# Sheet1.net
KiCad netlist of a schematic drawn in Altium Designer
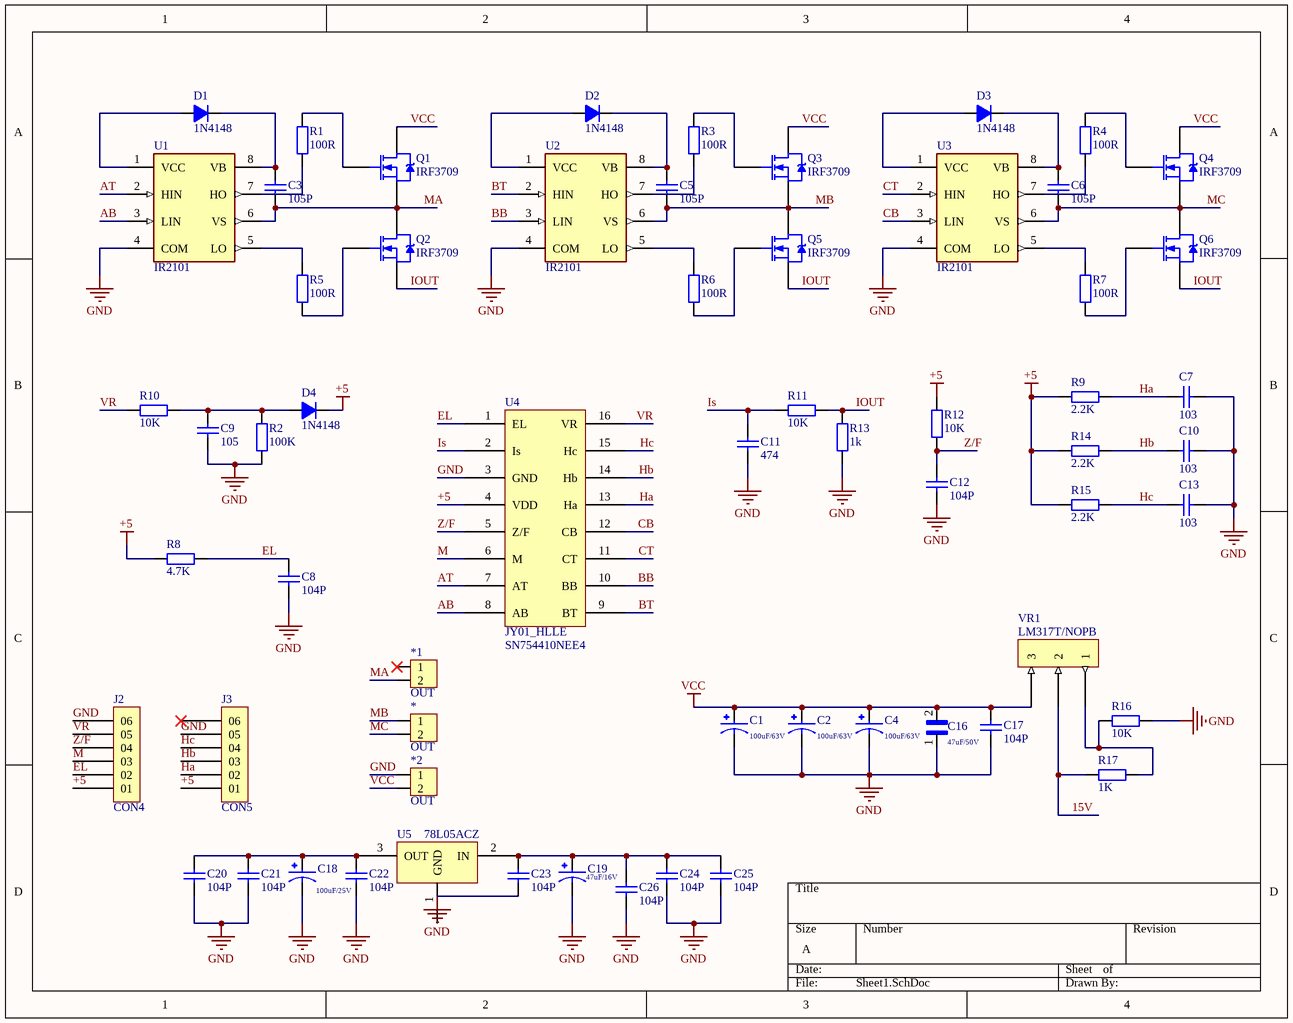
[diagram p0: Sheet1.SchDoc]

(export (version "E")
  (design (tool "Eeschema 10.0.6"))
  (components
    (comp (ref "*")
      (value "OUT")
      (footprint "VH3.96M-2 CONG")
      (libsource (lib "Altium_Duc Le_Lib(1)") (part "Header 2P VH3.96 Duc Cong"))
    )
    (comp (ref "*1")
      (value "OUT")
      (footprint "VH3.96M-2 CONG")
      (libsource (lib "Altium_Duc Le_Lib(1)") (part "Header 2P VH3.96 Duc Cong"))
    )
    (comp (ref "*2")
      (value "OUT")
      (footprint "VH3.96M-2 CONG")
      (libsource (lib "Altium_Duc Le_Lib(1)") (part "Header 2P VH3.96 Duc Cong"))
    )
    (comp (ref "C1")
      (value "100uF/63V")
      (footprint "CAP_EEVTG1J101Q")
      (description "100ÂµF 63V Aluminum Electrolytic Capacitors Radial, Can - SMD 260mOhm @ 100kHz 2000 Hrs @ 125Â°C")
      (fields (field (name "MP") "EEVTG1J101Q") (field (name "MF") "Panasonic"))
      (libsource (lib "100uF63VAEC") (part "EEVTG1J101Q"))
    )
    (comp (ref "C2")
      (value "100uF/63V")
      (footprint "CAP_EEVTG1J101Q")
      (description "100ÂµF 63V Aluminum Electrolytic Capacitors Radial, Can - SMD 260mOhm @ 100kHz 2000 Hrs @ 125Â°C")
      (fields (field (name "MP") "EEVTG1J101Q") (field (name "MF") "Panasonic"))
      (libsource (lib "100uF63VAEC") (part "EEVTG1J101Q"))
    )
    (comp (ref "C3")
      (value "105P")
      (footprint "tu 0805")
      (description "Dán")
      (libsource (lib "Altium_Lib_by_KhueNguyenCreator") (part "Tu 0805 472 50V 20%"))
    )
    (comp (ref "C4")
      (value "100uF/63V")
      (footprint "CAP_EEVTG1J101Q")
      (description "100ÂµF 63V Aluminum Electrolytic Capacitors Radial, Can - SMD 260mOhm @ 100kHz 2000 Hrs @ 125Â°C")
      (fields (field (name "MP") "EEVTG1J101Q") (field (name "MF") "Panasonic"))
      (libsource (lib "EEVTG1J101Q") (part "EEVTG1J101Q"))
    )
    (comp (ref "C5")
      (value "105P")
      (footprint "tu 0805")
      (description "Dán")
      (libsource (lib "Altium_Lib_by_KhueNguyenCreator") (part "Tu 0805 472 50V 20%"))
    )
    (comp (ref "C6")
      (value "105P")
      (footprint "tu 0805")
      (description "Dán")
      (libsource (lib "Altium_Lib_by_KhueNguyenCreator") (part "Tu 0805 472 50V 20%"))
    )
    (comp (ref "C7")
      (value "103")
      (footprint "tu 0805")
      (description "Dán")
      (libsource (lib "Altium_Lib_by_KhueNguyenCreator") (part "Tu 0805 471 50V 10%"))
    )
    (comp (ref "C8")
      (value "104P")
      (footprint "tu 0805")
      (description "Dán")
      (libsource (lib "Altium_Lib_by_KhueNguyenCreator") (part "Tu 0805 472 50V 20%"))
    )
    (comp (ref "C9")
      (value "105")
      (footprint "tu 0805")
      (description "Dán")
      (libsource (lib "Altium_Lib_by_KhueNguyenCreator") (part "Tu 0805 472 50V 20%"))
    )
    (comp (ref "C10")
      (value "103")
      (footprint "tu 0805")
      (description "Dán")
      (libsource (lib "Altium_Lib_by_KhueNguyenCreator") (part "Tu 0805 471 50V 10%"))
    )
    (comp (ref "C11")
      (value "474")
      (footprint "tu 0805")
      (description "Dán")
      (libsource (lib "Altium_Lib_by_KhueNguyenCreator") (part "Tu 0805 472 50V 20%"))
    )
    (comp (ref "C12")
      (value "104P")
      (footprint "tu 0805")
      (description "Dán")
      (libsource (lib "Altium_Lib_by_KhueNguyenCreator") (part "Tu 0805 472 50V 20%"))
    )
    (comp (ref "C13")
      (value "103")
      (footprint "tu 0805")
      (description "Dán")
      (libsource (lib "Altium_Lib_by_KhueNguyenCreator") (part "Tu 0805 471 50V 10%"))
    )
    (comp (ref "C16")
      (value "47uF/50V")
      (footprint "CAPC6050X550N")
      (fields (field (name "MF") "TDK") (field (name "MP") "CKG57NX7R1H476M500JJ"))
      (libsource (lib "47uF50VCeraCapa") (part "CKG57NX7R1H476M500JJ"))
    )
    (comp (ref "C17")
      (value "104P")
      (footprint "tu 0805")
      (description "Tu 0805 472 50V 20%\r\nSMD")
      (libsource (lib "Altium_Lib_by_KhueNguyenCreator") (part "Tu 0805 472 50V 20%"))
    )
    (comp (ref "C18")
      (value "100uF/25V")
      (footprint "CAP_EEEHA1E101AP")
      (description "100ÂµF 25V Aluminum Electrolytic Capacitors Radial, Can - SMD 1000 Hrs @ 105Â°C")
      (fields (field (name "MF") "Panasonic") (field (name "MP") "EEE-HA1E101AP"))
      (libsource (lib "100uF25VAEC") (part "EEEHA1E101AP"))
    )
    (comp (ref "C19")
      (value "47uF/16V")
      (footprint "CAP_EEE1CA470AP")
      (description "47ÂµF 16V Aluminum Electrolytic Capacitors Radial, Can - SMD 2000 Hrs @ 85Â°C")
      (fields (field (name "MP") "EEE-1CA470AP") (field (name "MF") "Panasonic"))
      (libsource (lib "47uF16V") (part "EEE1CA470AP"))
    )
    (comp (ref "C20")
      (value "104P")
      (footprint "tu 0805")
      (description "Dán")
      (libsource (lib "Altium_Lib_by_KhueNguyenCreator") (part "Tu 0805 472 50V 20%"))
    )
    (comp (ref "C21")
      (value "104P")
      (footprint "tu 0805")
      (description "Dán")
      (libsource (lib "Altium_Lib_by_KhueNguyenCreator") (part "Tu 0805 472 50V 20%"))
    )
    (comp (ref "C22")
      (value "104P")
      (footprint "tu 0805")
      (description "Dán")
      (libsource (lib "Altium_Lib_by_KhueNguyenCreator") (part "Tu 0805 472 50V 20%"))
    )
    (comp (ref "C23")
      (value "104P")
      (footprint "tu 0805")
      (description "Dán")
      (libsource (lib "Altium_Lib_by_KhueNguyenCreator") (part "Tu 0805 472 50V 20%"))
    )
    (comp (ref "C24")
      (value "104P")
      (footprint "tu 0805")
      (description "Dán")
      (libsource (lib "Altium_Lib_by_KhueNguyenCreator") (part "Tu 0805 472 50V 20%"))
    )
    (comp (ref "C25")
      (value "104P")
      (footprint "tu 0805")
      (description "Dán")
      (libsource (lib "Altium_Lib_by_KhueNguyenCreator") (part "Tu 0805 472 50V 20%"))
    )
    (comp (ref "C26")
      (value "104P")
      (footprint "tu 0805")
      (description "Dán")
      (libsource (lib "Altium_Lib_by_KhueNguyenCreator") (part "Tu 0805 472 50V 20%"))
    )
    (comp (ref "D1")
      (value "1N4148")
      (footprint "DIODE 0.5A")
      (description "Cắm")
      (libsource (lib "Altium_Lib_by_KhueNguyenCreator") (part "Diode 1N4148"))
    )
    (comp (ref "D2")
      (value "1N4148")
      (footprint "DIODE 0.5A")
      (description "Cắm")
      (libsource (lib "Altium_Lib_by_KhueNguyenCreator") (part "Diode 1N4148"))
    )
    (comp (ref "D3")
      (value "1N4148")
      (footprint "DIODE 0.5A")
      (description "Cắm")
      (libsource (lib "Altium_Lib_by_KhueNguyenCreator") (part "Diode 1N4148"))
    )
    (comp (ref "D4")
      (value "1N4148")
      (footprint "DIODE 0.5A")
      (description "Cắm")
      (libsource (lib "Altium_Lib_by_KhueNguyenCreator") (part "Diode 1N4148"))
    )
    (comp (ref "J2")
      (value "CON4")
      (footprint "VALCON_VH396-06S-010")
      (description "VH396 - Valcon 3.96mm 5A Wire-to-Board Straight Locking Power Connector")
      (fields (field (name "MF") "Valcon") (field (name "MP") "VH396-06S-010"))
      (libsource (lib "VH396-06S-010") (part "VH396-06S-010"))
    )
    (comp (ref "J3")
      (value "CON5")
      (footprint "VALCON_VH396-06S-010")
      (description "VH396 - Valcon 3.96mm 5A Wire-to-Board Straight Locking Power Connector")
      (fields (field (name "MF") "Valcon") (field (name "MP") "VH396-06S-010"))
      (libsource (lib "VH396-06S-010") (part "VH396-06S-010"))
    )
    (comp (ref "Q1")
      (value "IRF3709")
      (footprint "TO220")
      (description "N-Channel Power MOSFET")
      (libsource (lib "Altium_Lib_by_KhueNguyenCreator") (part "IRF3709 DIP"))
    )
    (comp (ref "Q2")
      (value "IRF3709")
      (footprint "TO220")
      (description "N-Channel Power MOSFET")
      (libsource (lib "Altium_Lib_by_KhueNguyenCreator") (part "IRF3709 DIP"))
    )
    (comp (ref "Q3")
      (value "IRF3709")
      (footprint "TO220")
      (description "N-Channel Power MOSFET")
      (libsource (lib "Altium_Lib_by_KhueNguyenCreator") (part "IRF3709 DIP"))
    )
    (comp (ref "Q4")
      (value "IRF3709")
      (footprint "TO220")
      (description "N-Channel Power MOSFET")
      (libsource (lib "Altium_Lib_by_KhueNguyenCreator") (part "IRF3709 DIP"))
    )
    (comp (ref "Q5")
      (value "IRF3709")
      (footprint "TO220")
      (description "N-Channel Power MOSFET")
      (libsource (lib "Altium_Lib_by_KhueNguyenCreator") (part "IRF3709 DIP"))
    )
    (comp (ref "Q6")
      (value "IRF3709")
      (footprint "TO220")
      (description "N-Channel Power MOSFET")
      (libsource (lib "Altium_Lib_by_KhueNguyenCreator") (part "IRF3709 DIP"))
    )
    (comp (ref "R1")
      (value "100R")
      (footprint "tro smd 0805")
      (description "Dán")
      (libsource (lib "Altium_Lib_by_KhueNguyenCreator") (part "Tro 0805 1% 1k"))
    )
    (comp (ref "R2")
      (value "100K")
      (footprint "tro smd 0805")
      (description "Dán")
      (libsource (lib "Altium_Lib_by_KhueNguyenCreator") (part "Tro 0805 1% 1k"))
    )
    (comp (ref "R3")
      (value "100R")
      (footprint "tro smd 0805")
      (description "Dán")
      (libsource (lib "Altium_Lib_by_KhueNguyenCreator") (part "Tro 0805 1% 1k"))
    )
    (comp (ref "R4")
      (value "100R")
      (footprint "tro smd 0805")
      (description "Dán")
      (libsource (lib "Altium_Lib_by_KhueNguyenCreator") (part "Tro 0805 1% 1k"))
    )
    (comp (ref "R5")
      (value "100R")
      (footprint "tro smd 0805")
      (description "Dán")
      (libsource (lib "Altium_Lib_by_KhueNguyenCreator") (part "Tro 0805 1% 1k"))
    )
    (comp (ref "R6")
      (value "100R")
      (footprint "tro smd 0805")
      (description "Dán")
      (libsource (lib "Altium_Lib_by_KhueNguyenCreator") (part "Tro 0805 1% 1k"))
    )
    (comp (ref "R7")
      (value "100R")
      (footprint "tro smd 0805")
      (description "Dán")
      (libsource (lib "Altium_Lib_by_KhueNguyenCreator") (part "Tro 0805 1% 1k"))
    )
    (comp (ref "R8")
      (value "4.7K")
      (footprint "tro smd 0805")
      (description "Dán")
      (libsource (lib "Altium_Lib_by_KhueNguyenCreator") (part "Tro 0805 1% 1k"))
    )
    (comp (ref "R9")
      (value "2.2K")
      (footprint "tro smd 0805")
      (description "Dán")
      (libsource (lib "Altium_Lib_by_KhueNguyenCreator") (part "Tro 0805 1% 1k"))
    )
    (comp (ref "R10")
      (value "10K")
      (footprint "tro smd 0805")
      (description "Dán")
      (libsource (lib "Altium_Lib_by_KhueNguyenCreator") (part "Tro 0805 1% 1k"))
    )
    (comp (ref "R11")
      (value "10K")
      (footprint "tro smd 0805")
      (description "Dán")
      (libsource (lib "Altium_Lib_by_KhueNguyenCreator") (part "Tro 0805 1% 1k"))
    )
    (comp (ref "R12")
      (value "10K")
      (footprint "tro smd 0805")
      (description "Dán")
      (libsource (lib "Altium_Lib_by_KhueNguyenCreator") (part "Tro 0805 1% 1k"))
    )
    (comp (ref "R13")
      (value "1k")
      (footprint "tro smd 0805")
      (description "Dán")
      (libsource (lib "Altium_Lib_by_KhueNguyenCreator") (part "Tro 0805 1% 1k"))
    )
    (comp (ref "R14")
      (value "2.2K")
      (footprint "tro smd 0805")
      (description "Dán")
      (libsource (lib "Altium_Lib_by_KhueNguyenCreator") (part "Tro 0805 1% 1k"))
    )
    (comp (ref "R15")
      (value "2.2K")
      (footprint "tro smd 0805")
      (description "Dán")
      (libsource (lib "Altium_Lib_by_KhueNguyenCreator") (part "Tro 0805 1% 1k"))
    )
    (comp (ref "R16")
      (value "10K")
      (footprint "tro smd 0805")
      (description "Dán")
      (libsource (lib "Altium_Lib_by_KhueNguyenCreator") (part "Tro 0805 1% 1k"))
    )
    (comp (ref "R17")
      (value "1K")
      (footprint "tro smd 0805")
      (description "Dán")
      (libsource (lib "Altium_Lib_by_KhueNguyenCreator") (part "Tro 0805 1% 1k"))
    )
    (comp (ref "U1")
      (value "IR2101")
      (footprint "DIL08")
      (description "Half-Bridge Gate Driver IC Non-Inverting 8-PDIP")
      (fields (field (name "MF") "Infineon") (field (name "DIGI-KEY_PART_NUMBER") "IR2101-ND"))
      (libsource (lib "IR2101") (part "IR2101"))
    )
    (comp (ref "U2")
      (value "IR2101")
      (footprint "DIL08")
      (description "Half-Bridge Gate Driver IC Non-Inverting 8-PDIP")
      (fields (field (name "MF") "Infineon") (field (name "DIGI-KEY_PART_NUMBER") "IR2101-ND"))
      (libsource (lib "IR2101") (part "IR2101"))
    )
    (comp (ref "U3")
      (value "IR2101")
      (footprint "DIL08")
      (description "Half-Bridge Gate Driver IC Non-Inverting 8-PDIP")
      (fields (field (name "MF") "Infineon") (field (name "DIGI-KEY_PART_NUMBER") "IR2101-ND"))
      (libsource (lib "IR2101") (part "IR2101"))
    )
    (comp (ref "U4")
      (value "SN754410NEE4")
      (footprint "DIP762W45P254L1980H508Q16:DIP762W45P254L1980H508Q16")
      (description "Quadruple Half-H Drivers 16-PDIP -40 to 85")
      (fields (field (name "MF") "Texas Instruments"))
      (libsource (lib "SN754410NEE4") (part "SN754410NEE4"))
    )
    (comp (ref "U5")
      (value "78L05ACZ")
      (footprint "TO-92")
      (description "Linear Voltage Regulator IC Positive Fixed 1 Output 100mA TO-92-3")
      (fields (field (name "MF") "STMicroelectronics"))
      (libsource (lib "78L05ACZ") (part "78L05ACZ"))
    )
    (comp (ref "VR1")
      (value "LM317T/NOPB")
      (footprint "TO254P1054X470X1955-3:TO254P1054X470X1955-3")
      (description "Linear Voltage Regulator IC Positive Adjustable 1 Output 1.5A TO-220-3")
      (fields (field (name "MF") "STMicroelectronics") (field (name "MP") "LM317T"))
      (libsource (lib "LM317T_NOPB") (part "LM317T/NOPB"))
    )
  )
  (nets
    (net (code "1") (name "+5") (class "Default")
      (node (ref "D4") (pin "2") (pinfunction "K_2") (pintype "passive"))
      (node (ref "J2") (pin "01") (pinfunction "01_01") (pintype "passive"))
      (node (ref "J3") (pin "01") (pinfunction "01_01") (pintype "passive"))
      (node (ref "R12") (pin "2") (pinfunction "2_2") (pintype "passive"))
      (node (ref "R14") (pin "1") (pinfunction "1_1") (pintype "passive"))
      (node (ref "R15") (pin "1") (pinfunction "1_1") (pintype "passive"))
      (node (ref "R8") (pin "1") (pinfunction "1_1") (pintype "passive"))
      (node (ref "R9") (pin "1") (pinfunction "1_1") (pintype "passive"))
      (node (ref "U4") (pin "4") (pinfunction "VDD_4") (pintype "passive"))
    )
    (net (code "2") (name "/15V") (class "Default")
      (node (ref "R17") (pin "1") (pinfunction "1_1") (pintype "passive"))
      (node (ref "VR1") (pin "Output") (pinfunction "2_Output") (pintype "input"))
    )
    (net (code "3") (name "/AB") (class "Default")
      (node (ref "U1") (pin "3") (pinfunction "LIN_3") (pintype "input"))
      (node (ref "U4") (pin "8") (pinfunction "AB_8") (pintype "passive"))
    )
    (net (code "4") (name "/AT") (class "Default")
      (node (ref "U1") (pin "2") (pinfunction "HIN_2") (pintype "input"))
      (node (ref "U4") (pin "7") (pinfunction "AT_7") (pintype "passive"))
    )
    (net (code "5") (name "/BB") (class "Default")
      (node (ref "U2") (pin "3") (pinfunction "LIN_3") (pintype "input"))
      (node (ref "U4") (pin "10") (pinfunction "BB_10") (pintype "passive"))
    )
    (net (code "6") (name "/BT") (class "Default")
      (node (ref "U2") (pin "2") (pinfunction "HIN_2") (pintype "input"))
      (node (ref "U4") (pin "9") (pinfunction "BT_9") (pintype "passive"))
    )
    (net (code "7") (name "/CB") (class "Default")
      (node (ref "U3") (pin "3") (pinfunction "LIN_3") (pintype "input"))
      (node (ref "U4") (pin "12") (pinfunction "CB_12") (pintype "passive"))
    )
    (net (code "8") (name "/CT") (class "Default")
      (node (ref "U3") (pin "2") (pinfunction "HIN_2") (pintype "input"))
      (node (ref "U4") (pin "11") (pinfunction "CT_11") (pintype "passive"))
    )
    (net (code "9") (name "/EL") (class "Default")
      (node (ref "C8") (pin "2") (pinfunction "2_2") (pintype "passive"))
      (node (ref "J2") (pin "02") (pinfunction "02_02") (pintype "passive"))
      (node (ref "R8") (pin "2") (pinfunction "2_2") (pintype "passive"))
      (node (ref "U4") (pin "1") (pinfunction "EL_1") (pintype "passive"))
    )
    (net (code "10") (name "/Ha") (class "Default")
      (node (ref "C7") (pin "1") (pinfunction "1_1") (pintype "passive"))
      (node (ref "J3") (pin "02") (pinfunction "02_02") (pintype "passive"))
      (node (ref "R9") (pin "2") (pinfunction "2_2") (pintype "passive"))
      (node (ref "U4") (pin "13") (pinfunction "Ha_13") (pintype "passive"))
    )
    (net (code "11") (name "/Hb") (class "Default")
      (node (ref "C10") (pin "1") (pinfunction "1_1") (pintype "passive"))
      (node (ref "J3") (pin "03") (pinfunction "03_03") (pintype "passive"))
      (node (ref "R14") (pin "2") (pinfunction "2_2") (pintype "passive"))
      (node (ref "U4") (pin "14") (pinfunction "Hb_14") (pintype "passive"))
    )
    (net (code "12") (name "/Hc") (class "Default")
      (node (ref "C13") (pin "1") (pinfunction "1_1") (pintype "passive"))
      (node (ref "J3") (pin "04") (pinfunction "04_04") (pintype "passive"))
      (node (ref "R15") (pin "2") (pinfunction "2_2") (pintype "passive"))
      (node (ref "U4") (pin "15") (pinfunction "Hc_15") (pintype "passive"))
    )
    (net (code "13") (name "/IOUT") (class "Default")
      (node (ref "Q2") (pin "3") (pinfunction "S_3") (pintype "passive"))
      (node (ref "Q5") (pin "3") (pinfunction "S_3") (pintype "passive"))
      (node (ref "Q6") (pin "3") (pinfunction "S_3") (pintype "passive"))
      (node (ref "R11") (pin "2") (pinfunction "2_2") (pintype "passive"))
      (node (ref "R13") (pin "2") (pinfunction "2_2") (pintype "passive"))
    )
    (net (code "14") (name "/Is") (class "Default")
      (node (ref "C11") (pin "1") (pinfunction "1_1") (pintype "passive"))
      (node (ref "R11") (pin "1") (pinfunction "1_1") (pintype "passive"))
      (node (ref "U4") (pin "2") (pinfunction "Is_2") (pintype "passive"))
    )
    (net (code "15") (name "/M") (class "Default")
      (node (ref "J2") (pin "03") (pinfunction "03_03") (pintype "passive"))
      (node (ref "U4") (pin "6") (pinfunction "M_6") (pintype "passive"))
    )
    (net (code "16") (name "/MA") (class "Default")
      (node (ref "*1") (pin "2") (pinfunction "2_2") (pintype "passive"))
      (node (ref "C3") (pin "2") (pinfunction "2_2") (pintype "passive"))
      (node (ref "Q1") (pin "3") (pinfunction "S_3") (pintype "passive"))
      (node (ref "Q2") (pin "2") (pinfunction "D_2") (pintype "passive"))
      (node (ref "U1") (pin "6") (pinfunction "VS_6") (pintype "output"))
    )
    (net (code "17") (name "/MB") (class "Default")
      (node (ref "*") (pin "1") (pinfunction "1_1") (pintype "passive"))
      (node (ref "C5") (pin "2") (pinfunction "2_2") (pintype "passive"))
      (node (ref "Q3") (pin "3") (pinfunction "S_3") (pintype "passive"))
      (node (ref "Q5") (pin "2") (pinfunction "D_2") (pintype "passive"))
      (node (ref "U2") (pin "6") (pinfunction "VS_6") (pintype "output"))
    )
    (net (code "18") (name "/MC") (class "Default")
      (node (ref "*") (pin "2") (pinfunction "2_2") (pintype "passive"))
      (node (ref "C6") (pin "2") (pinfunction "2_2") (pintype "passive"))
      (node (ref "Q4") (pin "3") (pinfunction "S_3") (pintype "passive"))
      (node (ref "Q6") (pin "2") (pinfunction "D_2") (pintype "passive"))
      (node (ref "U3") (pin "6") (pinfunction "VS_6") (pintype "output"))
    )
    (net (code "19") (name "/VR") (class "Default")
      (node (ref "J2") (pin "05") (pinfunction "05_05") (pintype "passive"))
      (node (ref "R10") (pin "1") (pinfunction "1_1") (pintype "passive"))
      (node (ref "U4") (pin "16") (pinfunction "VR_16") (pintype "passive"))
    )
    (net (code "20") (name "/Z{slash}F") (class "Default")
      (node (ref "C12") (pin "1") (pinfunction "1_1") (pintype "passive"))
      (node (ref "J2") (pin "04") (pinfunction "04_04") (pintype "passive"))
      (node (ref "R12") (pin "1") (pinfunction "1_1") (pintype "passive"))
      (node (ref "U4") (pin "5") (pinfunction "Z/F_5") (pintype "passive"))
    )
    (net (code "21") (name "GND") (class "Default")
      (node (ref "*2") (pin "1") (pinfunction "1_1") (pintype "passive"))
      (node (ref "C1") (pin "2") (pinfunction "2_2") (pintype "passive"))
      (node (ref "C10") (pin "2") (pinfunction "2_2") (pintype "passive"))
      (node (ref "C11") (pin "2") (pinfunction "2_2") (pintype "passive"))
      (node (ref "C12") (pin "2") (pinfunction "2_2") (pintype "passive"))
      (node (ref "C13") (pin "2") (pinfunction "2_2") (pintype "passive"))
      (node (ref "C16") (pin "1") (pinfunction "1_1") (pintype "passive"))
      (node (ref "C17") (pin "2") (pinfunction "2_2") (pintype "passive"))
      (node (ref "C18") (pin "2") (pinfunction "2_2") (pintype "passive"))
      (node (ref "C19") (pin "2") (pinfunction "2_2") (pintype "passive"))
      (node (ref "C2") (pin "2") (pinfunction "2_2") (pintype "passive"))
      (node (ref "C20") (pin "2") (pinfunction "2_2") (pintype "passive"))
      (node (ref "C21") (pin "2") (pinfunction "2_2") (pintype "passive"))
      (node (ref "C22") (pin "2") (pinfunction "2_2") (pintype "passive"))
      (node (ref "C23") (pin "2") (pinfunction "2_2") (pintype "passive"))
      (node (ref "C24") (pin "2") (pinfunction "2_2") (pintype "passive"))
      (node (ref "C25") (pin "2") (pinfunction "2_2") (pintype "passive"))
      (node (ref "C26") (pin "2") (pinfunction "2_2") (pintype "passive"))
      (node (ref "C4") (pin "2") (pinfunction "2_2") (pintype "passive"))
      (node (ref "C7") (pin "2") (pinfunction "2_2") (pintype "passive"))
      (node (ref "C8") (pin "1") (pinfunction "1_1") (pintype "passive"))
      (node (ref "C9") (pin "2") (pinfunction "2_2") (pintype "passive"))
      (node (ref "J2") (pin "06") (pinfunction "06_06") (pintype "passive"))
      (node (ref "J3") (pin "05") (pinfunction "05_05") (pintype "passive"))
      (node (ref "R13") (pin "1") (pinfunction "1_1") (pintype "passive"))
      (node (ref "R16") (pin "2") (pinfunction "2_2") (pintype "passive"))
      (node (ref "R2") (pin "1") (pinfunction "1_1") (pintype "passive"))
      (node (ref "U1") (pin "4") (pinfunction "COM_4") (pintype "power_in"))
      (node (ref "U2") (pin "4") (pinfunction "COM_4") (pintype "power_in"))
      (node (ref "U3") (pin "4") (pinfunction "COM_4") (pintype "power_in"))
      (node (ref "U4") (pin "3") (pinfunction "GND_3") (pintype "passive"))
    )
    (net (code "22") (name "Net-(D1-A)") (class "Default")
      (node (ref "D1") (pin "1") (pinfunction "A_1") (pintype "passive"))
      (node (ref "U1") (pin "1") (pinfunction "VCC_1") (pintype "power_in"))
    )
    (net (code "23") (name "Net-(D1-K)") (class "Default")
      (node (ref "C3") (pin "1") (pinfunction "1_1") (pintype "passive"))
      (node (ref "D1") (pin "2") (pinfunction "K_2") (pintype "passive"))
      (node (ref "U1") (pin "8") (pinfunction "VB_8") (pintype "power_in"))
    )
    (net (code "24") (name "Net-(D2-A)") (class "Default")
      (node (ref "D2") (pin "1") (pinfunction "A_1") (pintype "passive"))
      (node (ref "U2") (pin "1") (pinfunction "VCC_1") (pintype "power_in"))
    )
    (net (code "25") (name "Net-(D2-K)") (class "Default")
      (node (ref "C5") (pin "1") (pinfunction "1_1") (pintype "passive"))
      (node (ref "D2") (pin "2") (pinfunction "K_2") (pintype "passive"))
      (node (ref "U2") (pin "8") (pinfunction "VB_8") (pintype "power_in"))
    )
    (net (code "26") (name "Net-(D3-A)") (class "Default")
      (node (ref "D3") (pin "1") (pinfunction "A_1") (pintype "passive"))
      (node (ref "U3") (pin "1") (pinfunction "VCC_1") (pintype "power_in"))
    )
    (net (code "27") (name "Net-(D3-K)") (class "Default")
      (node (ref "C6") (pin "1") (pinfunction "1_1") (pintype "passive"))
      (node (ref "D3") (pin "2") (pinfunction "K_2") (pintype "passive"))
      (node (ref "U3") (pin "8") (pinfunction "VB_8") (pintype "power_in"))
    )
    (net (code "28") (name "Net-(D4-A)") (class "Default")
      (node (ref "C9") (pin "1") (pinfunction "1_1") (pintype "passive"))
      (node (ref "D4") (pin "1") (pinfunction "A_1") (pintype "passive"))
      (node (ref "R10") (pin "2") (pinfunction "2_2") (pintype "passive"))
      (node (ref "R2") (pin "2") (pinfunction "2_2") (pintype "passive"))
    )
    (net (code "29") (name "Net-(Q1-G)") (class "Default")
      (node (ref "Q1") (pin "1") (pinfunction "G_1") (pintype "passive"))
      (node (ref "R1") (pin "2") (pinfunction "2_2") (pintype "passive"))
    )
    (net (code "30") (name "Net-(Q2-G)") (class "Default")
      (node (ref "Q2") (pin "1") (pinfunction "G_1") (pintype "passive"))
      (node (ref "R5") (pin "1") (pinfunction "1_1") (pintype "passive"))
    )
    (net (code "31") (name "Net-(Q3-G)") (class "Default")
      (node (ref "Q3") (pin "1") (pinfunction "G_1") (pintype "passive"))
      (node (ref "R3") (pin "2") (pinfunction "2_2") (pintype "passive"))
    )
    (net (code "32") (name "Net-(Q4-G)") (class "Default")
      (node (ref "Q4") (pin "1") (pinfunction "G_1") (pintype "passive"))
      (node (ref "R4") (pin "2") (pinfunction "2_2") (pintype "passive"))
    )
    (net (code "33") (name "Net-(Q5-G)") (class "Default")
      (node (ref "Q5") (pin "1") (pinfunction "G_1") (pintype "passive"))
      (node (ref "R6") (pin "1") (pinfunction "1_1") (pintype "passive"))
    )
    (net (code "34") (name "Net-(Q6-G)") (class "Default")
      (node (ref "Q6") (pin "1") (pinfunction "G_1") (pintype "passive"))
      (node (ref "R7") (pin "1") (pinfunction "1_1") (pintype "passive"))
    )
    (net (code "35") (name "Net-(U1-HO)") (class "Default")
      (node (ref "R1") (pin "1") (pinfunction "1_1") (pintype "passive"))
      (node (ref "U1") (pin "7") (pinfunction "HO_7") (pintype "output"))
    )
    (net (code "36") (name "Net-(U1-LO)") (class "Default")
      (node (ref "R5") (pin "2") (pinfunction "2_2") (pintype "passive"))
      (node (ref "U1") (pin "5") (pinfunction "LO_5") (pintype "output"))
    )
    (net (code "37") (name "Net-(U2-HO)") (class "Default")
      (node (ref "R3") (pin "1") (pinfunction "1_1") (pintype "passive"))
      (node (ref "U2") (pin "7") (pinfunction "HO_7") (pintype "output"))
    )
    (net (code "38") (name "Net-(U2-LO)") (class "Default")
      (node (ref "R6") (pin "2") (pinfunction "2_2") (pintype "passive"))
      (node (ref "U2") (pin "5") (pinfunction "LO_5") (pintype "output"))
    )
    (net (code "39") (name "Net-(U3-HO)") (class "Default")
      (node (ref "R4") (pin "1") (pinfunction "1_1") (pintype "passive"))
      (node (ref "U3") (pin "7") (pinfunction "HO_7") (pintype "output"))
    )
    (net (code "40") (name "Net-(U3-LO)") (class "Default")
      (node (ref "R7") (pin "2") (pinfunction "2_2") (pintype "passive"))
      (node (ref "U3") (pin "5") (pinfunction "LO_5") (pintype "output"))
    )
    (net (code "41") (name "Net-(U5-IN)") (class "Default")
      (node (ref "C19") (pin "1") (pinfunction "1_1") (pintype "passive"))
      (node (ref "C23") (pin "1") (pinfunction "1_1") (pintype "passive"))
      (node (ref "C24") (pin "1") (pinfunction "1_1") (pintype "passive"))
      (node (ref "C25") (pin "1") (pinfunction "1_1") (pintype "passive"))
      (node (ref "C26") (pin "1") (pinfunction "1_1") (pintype "passive"))
      (node (ref "U5") (pin "2") (pinfunction "IN_2") (pintype "passive"))
    )
    (net (code "42") (name "Net-(U5-OUT)") (class "Default")
      (node (ref "C18") (pin "1") (pinfunction "1_1") (pintype "passive"))
      (node (ref "C20") (pin "1") (pinfunction "1_1") (pintype "passive"))
      (node (ref "C21") (pin "1") (pinfunction "1_1") (pintype "passive"))
      (node (ref "C22") (pin "1") (pinfunction "1_1") (pintype "passive"))
      (node (ref "U5") (pin "3") (pinfunction "OUT_3") (pintype "passive"))
    )
    (net (code "43") (name "Net-(VR1-1)") (class "Default")
      (node (ref "R16") (pin "1") (pinfunction "1_1") (pintype "passive"))
      (node (ref "R17") (pin "2") (pinfunction "2_2") (pintype "passive"))
      (node (ref "VR1") (pin "ADJ") (pinfunction "1_ADJ") (pintype "output"))
    )
    (net (code "44") (name "VCC") (class "Default")
      (node (ref "*2") (pin "2") (pinfunction "2_2") (pintype "passive"))
      (node (ref "C1") (pin "1") (pinfunction "1_1") (pintype "passive"))
      (node (ref "C16") (pin "2") (pinfunction "2_2") (pintype "passive"))
      (node (ref "C17") (pin "1") (pinfunction "1_1") (pintype "passive"))
      (node (ref "C2") (pin "1") (pinfunction "1_1") (pintype "passive"))
      (node (ref "C4") (pin "1") (pinfunction "1_1") (pintype "passive"))
      (node (ref "Q1") (pin "2") (pinfunction "D_2") (pintype "passive"))
      (node (ref "Q3") (pin "2") (pinfunction "D_2") (pintype "passive"))
      (node (ref "Q4") (pin "2") (pinfunction "D_2") (pintype "passive"))
      (node (ref "VR1") (pin "Input") (pinfunction "3_Input") (pintype "input"))
    )
    (net (code "45") (name "unconnected-(*1-Pad1)") (class "Default")
      (node (ref "*1") (pin "1") (pinfunction "1_1") (pintype "passive+no_connect"))
    )
    (net (code "46") (name "unconnected-(J3-Pad06)") (class "Default")
      (node (ref "J3") (pin "06") (pinfunction "06_06") (pintype "passive+no_connect"))
    )
    (net (code "47") (name "unconnected-(U5-GND-Pad1)") (class "Default")
      (node (ref "U5") (pin "1") (pinfunction "GND_1") (pintype "passive"))
    )
  )
)
